# StationSolPortative.net
KiCad netlist of a schematic drawn in Altium Designer
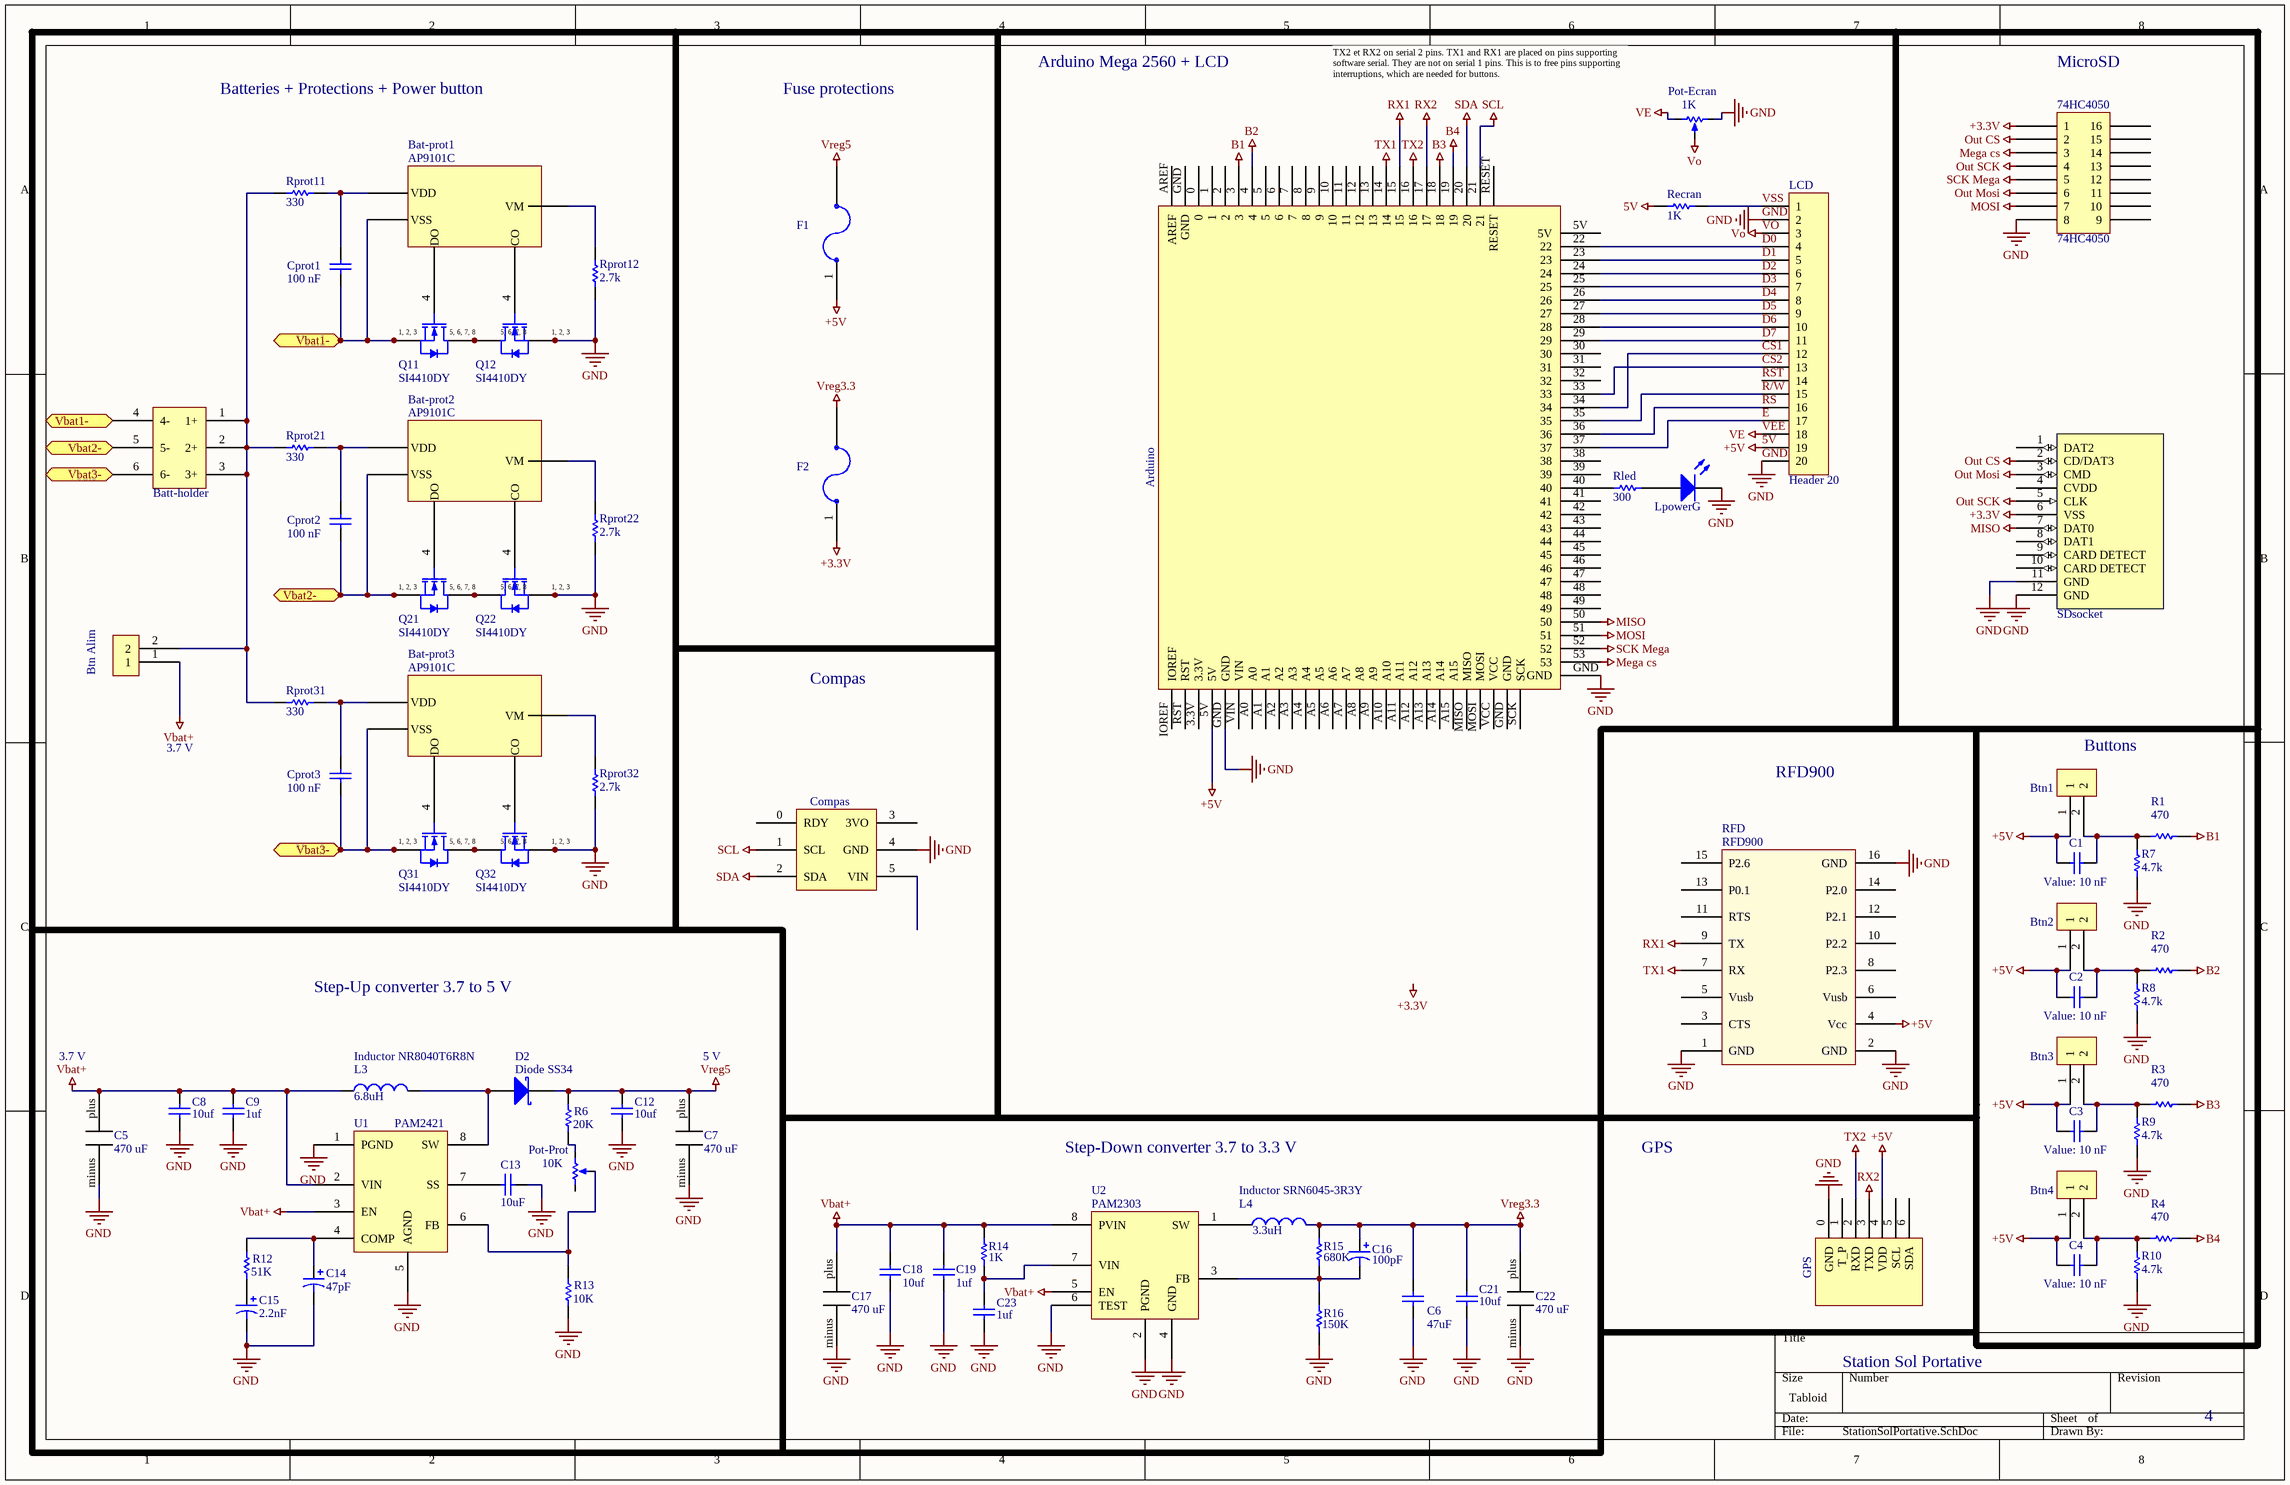
[diagram p0: StationSolPortative.SchDoc]

(export (version "E")
  (design (tool "Eeschema 10.0.6"))
  (components
    (comp (ref "74HC4050")
      (value "74HC4050")
      (footprint "DIP16_74HC4050")
      (libsource (lib "74HC4050") (part "74HC4050"))
    )
    (comp (ref "Arduino")
      (value "ArduinoMega2560")
      (footprint "ArduinoMega2560")
      (libsource (lib "ArduinoMega2560") (part "ArduinoMega2560"))
    )
    (comp (ref "Bat-prot1")
      (value "AP9101C")
      (footprint "SOT26")
      (fields (field (name "NAME") "AP9101C"))
      (libsource (lib "surfaceMount") (part "AP9101C"))
    )
    (comp (ref "Bat-prot2")
      (value "AP9101C")
      (footprint "SOT26")
      (fields (field (name "NAME") "AP9101C"))
      (libsource (lib "surfaceMount") (part "AP9101C"))
    )
    (comp (ref "Bat-prot3")
      (value "AP9101C")
      (footprint "SOT26")
      (fields (field (name "NAME") "AP9101C"))
      (libsource (lib "surfaceMount") (part "AP9101C"))
    )
    (comp (ref "Batt-holder")
      (value "BH-BK-18650-PC6-ND")
      (footprint "BH-BK-18650-PC6-ND")
      (libsource (lib "BatterieHolder") (part "BH-BK-18650-PC6-ND"))
    )
    (comp (ref "Btn Alim")
      (value "MAT100_2PINS")
      (footprint "MTA100_2PINS")
      (libsource (lib "MTA_connectors") (part "MAT100_2PINS"))
    )
    (comp (ref "Btn1")
      (value "MAT100_2PINS")
      (footprint "MTA100_2PINS")
      (libsource (lib "") (part "MAT100_2PINS_1"))
    )
    (comp (ref "Btn2")
      (value "MAT100_2PINS")
      (footprint "MTA100_2PINS")
      (libsource (lib "") (part "MAT100_2PINS_1"))
    )
    (comp (ref "Btn3")
      (value "MAT100_2PINS")
      (footprint "MTA100_2PINS")
      (libsource (lib "") (part "MAT100_2PINS_1"))
    )
    (comp (ref "Btn4")
      (value "MAT100_2PINS")
      (footprint "MTA100_2PINS")
      (libsource (lib "") (part "MAT100_2PINS_1"))
    )
    (comp (ref "C1")
      (value "10 nF")
      (footprint "CAP 0805 - N")
      (libsource (lib "surfaceMount") (part "Condensateur smd"))
    )
    (comp (ref "C2")
      (value "10 nF")
      (footprint "CAP 0805 - N")
      (libsource (lib "surfaceMount") (part "Condensateur smd"))
    )
    (comp (ref "C3")
      (value "10 nF")
      (footprint "CAP 0805 - N")
      (libsource (lib "surfaceMount") (part "Condensateur smd"))
    )
    (comp (ref "C4")
      (value "10 nF")
      (footprint "CAP 0805 - N")
      (libsource (lib "surfaceMount") (part "Condensateur smd"))
    )
    (comp (ref "C5")
      (value "470 uF")
      (footprint "Gros condensateur")
      (libsource (lib "surfaceMount") (part "Gros condensateur"))
    )
    (comp (ref "C6")
      (value "47uF")
      (footprint "C1210")
      (description "Capacitor (Semiconductor SIM Model)")
      (fields (field (name "Comment") "Cap Semi") (field (name "PUBLISHER") "Altium Limited"))
      (libsource (lib "Miscellaneous Devices") (part "Cap Semi"))
    )
    (comp (ref "C7")
      (value "470 uF")
      (footprint "Gros condensateur")
      (libsource (lib "surfaceMount") (part "Gros condensateur"))
    )
    (comp (ref "C8")
      (value "10uf")
      (footprint "CAP 0805 - N")
      (libsource (lib "surfaceMount") (part "Condensateur smd"))
    )
    (comp (ref "C9")
      (value "1uf")
      (footprint "CAP 0805 - N")
      (libsource (lib "surfaceMount") (part "Condensateur smd"))
    )
    (comp (ref "C12")
      (value "10uf")
      (footprint "CAP 0805 - N")
      (libsource (lib "surfaceMount") (part "Condensateur smd"))
    )
    (comp (ref "C13")
      (value "10uF")
      (footprint "CAP 0805 - N")
      (libsource (lib "surfaceMount") (part "Condensateur smd"))
    )
    (comp (ref "C14")
      (value "47pF")
      (footprint "CAP 0805 - N")
      (description "Polarized Capacitor (Radial)")
      (fields (field (name "Comment") "Cap Pol1") (field (name "PUBLISHER") "Altium Limited"))
      (libsource (lib "Miscellaneous Devices") (part "Cap Pol1"))
    )
    (comp (ref "C15")
      (value "2.2nF")
      (footprint "CAP 0805 - N")
      (description "Polarized Capacitor (Radial)")
      (fields (field (name "Comment") "Cap Pol1") (field (name "PUBLISHER") "Altium Limited"))
      (libsource (lib "Miscellaneous Devices") (part "Cap Pol1"))
    )
    (comp (ref "C16")
      (value "100pF")
      (footprint "CAP 0805 - N")
      (description "Polarized Capacitor (Radial)")
      (fields (field (name "Comment") "Cap Pol1") (field (name "PUBLISHER") "Altium Limited"))
      (libsource (lib "Miscellaneous Devices") (part "Cap Pol1"))
    )
    (comp (ref "C17")
      (value "470 uF")
      (footprint "Gros condensateur")
      (libsource (lib "surfaceMount") (part "Gros condensateur"))
    )
    (comp (ref "C18")
      (value "10uf")
      (footprint "CAP 0805 - N")
      (libsource (lib "surfaceMount") (part "Condensateur smd"))
    )
    (comp (ref "C19")
      (value "1uf")
      (footprint "CAP 0805 - N")
      (libsource (lib "surfaceMount") (part "Condensateur smd"))
    )
    (comp (ref "C21")
      (value "10uf")
      (footprint "CAP 0805 - N")
      (libsource (lib "surfaceMount") (part "Condensateur smd"))
    )
    (comp (ref "C22")
      (value "470 uF")
      (footprint "Gros condensateur")
      (libsource (lib "surfaceMount") (part "Gros condensateur"))
    )
    (comp (ref "C23")
      (value "1uf")
      (footprint "CAP 0805 - N")
      (libsource (lib "surfaceMount") (part "Condensateur smd"))
    )
    (comp (ref "Compas")
      (value "HMC5883L")
      (footprint "Adafruit:HMC5883L")
      (description "Compass")
      (libsource (lib "Adafruit") (part "HMC5883L"))
    )
    (comp (ref "Cprot1")
      (value "100 nF")
      (footprint "CAP 0805 - N")
      (libsource (lib "surfaceMount") (part "Condensateur smd"))
    )
    (comp (ref "Cprot2")
      (value "100 nF")
      (footprint "CAP 0805 - N")
      (libsource (lib "surfaceMount") (part "Condensateur smd"))
    )
    (comp (ref "Cprot3")
      (value "100 nF")
      (footprint "CAP 0805 - N")
      (libsource (lib "surfaceMount") (part "Condensateur smd"))
    )
    (comp (ref "D2")
      (value "Diode SS34")
      (footprint "Diode")
      (description "Schottky Rectifier")
      (fields (field (name "PUBLISHER") "Altium Limited"))
      (libsource (lib "Miscellaneous Devices") (part "Diode 10TQ035"))
    )
    (comp (ref "F1")
      (value "Fuse")
      (footprint "Fuse Holder 3mm")
      (libsource (lib "Lib Sch Compo") (part "Fuse"))
    )
    (comp (ref "F2")
      (value "Fuse")
      (footprint "Fuse Holder 3mm")
      (libsource (lib "Lib Sch Compo") (part "Fuse"))
    )
    (comp (ref "gps") (value "GPS") (footprint "PAM-7Q GPS") (libsource (lib "Paralax") (part "Pam-Q7 GPS")))
    (comp (ref "L3")
      (value "Inductor NR8040T6R8N")
      (footprint "Inductance 6.8uH")
      (description "Inductor")
      (fields (field (name "ALTIUM_VALUE") "6.8uH") (field (name "PUBLISHER") "Altium Limited"))
      (libsource (lib "Miscellaneous Devices") (part "Inductor"))
    )
    (comp (ref "L4")
      (value "Inductor SRN6045-3R3Y")
      (footprint "Inductance")
      (description "Inductor")
      (fields (field (name "ALTIUM_VALUE") "3.3uH") (field (name "PUBLISHER") "Altium Limited"))
      (libsource (lib "Miscellaneous Devices") (part "Inductor"))
    )
    (comp (ref "LCD")
      (value "Header 20")
      (footprint "Miscellaneous Connectors:HDR2X10")
      (description "Header, 20-Pin")
      (fields (field (name "PUBLISHER") "Altium Limited"))
      (libsource (lib "Miscellaneous Connectors") (part "Header 20"))
    )
    (comp (ref "LpowerG")
      (value "LED 1206")
      (footprint "LED - 1206")
      (libsource (lib "surfaceMount") (part "LED"))
    )
    (comp (ref "Pot-Ecran")
      (value "1K")
      (footprint "Trim 67WR")
      (description "Resistor Trimmer")
      (fields (field (name "Comment") "Res Pot"))
      (libsource (lib "Lib Sch Compo") (part "Res Pot"))
    )
    (comp (ref "Pot-Prot")
      (value "10K")
      (footprint "Trim 67WR")
      (description "Resistor Trimmer")
      (fields (field (name "Comment") "Res Pot"))
      (libsource (lib "Lib Sch Compo") (part "Res Pot"))
    )
    (comp (ref "Q11")
      (value "SI4410DY")
      (footprint "SO-8_N")
      (description "N-Channel 30V (D-S)  MOSFET")
      (fields (field (name "PUBLISHER") "Altium Limited"))
      (libsource (lib "Vishay Siliconix Discrete MOSFET") (part "SI4410DY"))
    )
    (comp (ref "Q12")
      (value "SI4410DY")
      (footprint "SO-8_N")
      (description "N-Channel 30V (D-S)  MOSFET")
      (fields (field (name "PUBLISHER") "Altium Limited"))
      (libsource (lib "Vishay Siliconix Discrete MOSFET") (part "SI4410DY"))
    )
    (comp (ref "Q21")
      (value "SI4410DY")
      (footprint "SO-8_N")
      (description "N-Channel 30V (D-S)  MOSFET")
      (fields (field (name "PUBLISHER") "Altium Limited"))
      (libsource (lib "Vishay Siliconix Discrete MOSFET") (part "SI4410DY"))
    )
    (comp (ref "Q22")
      (value "SI4410DY")
      (footprint "SO-8_N")
      (description "N-Channel 30V (D-S)  MOSFET")
      (fields (field (name "PUBLISHER") "Altium Limited"))
      (libsource (lib "Vishay Siliconix Discrete MOSFET") (part "SI4410DY"))
    )
    (comp (ref "Q31")
      (value "SI4410DY")
      (footprint "SO-8_N")
      (description "N-Channel 30V (D-S)  MOSFET")
      (fields (field (name "PUBLISHER") "Altium Limited"))
      (libsource (lib "Vishay Siliconix Discrete MOSFET") (part "SI4410DY"))
    )
    (comp (ref "Q32")
      (value "SI4410DY")
      (footprint "SO-8_N")
      (description "N-Channel 30V (D-S)  MOSFET")
      (fields (field (name "PUBLISHER") "Altium Limited"))
      (libsource (lib "Vishay Siliconix Discrete MOSFET") (part "SI4410DY"))
    )
    (comp (ref "R1")
      (value "470")
      (footprint "Res 0805 - N")
      (fields (field (name "Comment") "Res smd"))
      (libsource (lib "surfaceMount") (part "Res smd"))
    )
    (comp (ref "R2")
      (value "470")
      (footprint "Res 0805 - N")
      (fields (field (name "Comment") "Res smd"))
      (libsource (lib "surfaceMount") (part "Res smd"))
    )
    (comp (ref "R3")
      (value "470")
      (footprint "Res 0805 - N")
      (fields (field (name "Comment") "Res smd"))
      (libsource (lib "surfaceMount") (part "Res smd"))
    )
    (comp (ref "R4")
      (value "470")
      (footprint "Res 0805 - N")
      (fields (field (name "Comment") "Res smd"))
      (libsource (lib "surfaceMount") (part "Res smd"))
    )
    (comp (ref "R6")
      (value "20K")
      (footprint "Res 0805 - N")
      (description "Resistor")
      (fields (field (name "Comment") "Res1") (field (name "PUBLISHER") "Altium Limited"))
      (libsource (lib "Miscellaneous Devices") (part "Res1"))
    )
    (comp (ref "R7")
      (value "4.7k")
      (footprint "Res 0805 - N")
      (fields (field (name "Comment") "Res smd"))
      (libsource (lib "surfaceMount") (part "Res smd"))
    )
    (comp (ref "R8")
      (value "4.7k")
      (footprint "Res 0805 - N")
      (fields (field (name "Comment") "Res smd"))
      (libsource (lib "surfaceMount") (part "Res smd"))
    )
    (comp (ref "R9")
      (value "4.7k")
      (footprint "Res 0805 - N")
      (fields (field (name "Comment") "Res smd"))
      (libsource (lib "surfaceMount") (part "Res smd"))
    )
    (comp (ref "R10")
      (value "4.7k")
      (footprint "Res 0805 - N")
      (fields (field (name "Comment") "Res smd"))
      (libsource (lib "surfaceMount") (part "Res smd"))
    )
    (comp (ref "R12")
      (value "51K")
      (footprint "Res 0805 - N")
      (description "Resistor")
      (fields (field (name "Comment") "Res1") (field (name "PUBLISHER") "Altium Limited"))
      (libsource (lib "Miscellaneous Devices") (part "Res1"))
    )
    (comp (ref "R13")
      (value "10K")
      (footprint "Res 0805 - N")
      (description "Resistor")
      (fields (field (name "Comment") "Res1") (field (name "PUBLISHER") "Altium Limited"))
      (libsource (lib "Miscellaneous Devices") (part "Res1"))
    )
    (comp (ref "R14")
      (value "1K")
      (footprint "Res 0805 - N")
      (description "Resistor")
      (fields (field (name "Comment") "Res1") (field (name "PUBLISHER") "Altium Limited"))
      (libsource (lib "Miscellaneous Devices") (part "Res1"))
    )
    (comp (ref "R15")
      (value "680K")
      (footprint "Res 0805 - N")
      (description "Resistor")
      (fields (field (name "Comment") "Res1") (field (name "PUBLISHER") "Altium Limited"))
      (libsource (lib "Miscellaneous Devices") (part "Res1"))
    )
    (comp (ref "R16")
      (value "150K")
      (footprint "Res 0805 - N")
      (description "Resistor")
      (fields (field (name "Comment") "Res1") (field (name "PUBLISHER") "Altium Limited"))
      (libsource (lib "Miscellaneous Devices") (part "Res1"))
    )
    (comp (ref "Recran")
      (value "1K")
      (footprint "Res 0805 - N")
      (fields (field (name "Comment") "Res smd"))
      (libsource (lib "surfaceMount") (part "Res smd"))
    )
    (comp (ref "RFD")
      (value "Component_1")
      (footprint "RFD900")
      (libsource (lib "RFD900") (part "Component_1"))
    )
    (comp (ref "Rled")
      (value "300")
      (footprint "Res 0805 - N")
      (fields (field (name "Comment") "Res smd"))
      (libsource (lib "surfaceMount") (part "Res smd"))
    )
    (comp (ref "Rprot11")
      (value "330")
      (footprint "Res 0805 - N")
      (fields (field (name "Comment") "Res smd"))
      (libsource (lib "surfaceMount") (part "Res smd"))
    )
    (comp (ref "Rprot12")
      (value "2.7k")
      (footprint "Res 0805 - N")
      (fields (field (name "Comment") "Res smd"))
      (libsource (lib "surfaceMount") (part "Res smd"))
    )
    (comp (ref "Rprot21")
      (value "330")
      (footprint "Res 0805 - N")
      (fields (field (name "Comment") "Res smd"))
      (libsource (lib "surfaceMount") (part "Res smd"))
    )
    (comp (ref "Rprot22")
      (value "2.7k")
      (footprint "Res 0805 - N")
      (fields (field (name "Comment") "Res smd"))
      (libsource (lib "surfaceMount") (part "Res smd"))
    )
    (comp (ref "Rprot31")
      (value "330")
      (footprint "Res 0805 - N")
      (fields (field (name "Comment") "Res smd"))
      (libsource (lib "surfaceMount") (part "Res smd"))
    )
    (comp (ref "Rprot32")
      (value "2.7k")
      (footprint "Res 0805 - N")
      (fields (field (name "Comment") "Res smd"))
      (libsource (lib "surfaceMount") (part "Res smd"))
    )
    (comp (ref "SDsocket")
      (value "Carte micro SD")
      (footprint "Carte SD")
      (libsource (lib "surfaceMount") (part "Carte SD"))
    )
    (comp (ref "U1")
      (value "PAM2421")
      (footprint "SOP8")
      (description "3A PWM STEP-UP DC-DC CONVERTER")
      (fields (field (name "ALTIUM_UNNAMED_1") "PAM2421"))
      (libsource (lib "surfaceMount") (part "PAM2421"))
    )
    (comp (ref "U2")
      (value "PAM2320")
      (footprint "SOP8")
      (description "3A LOW NOISE STEP-DOWN DC-DC CONVERTER")
      (fields (field (name "NAME") "PAM2303"))
      (libsource (lib "PAM2303") (part "PAM2320"))
    )
  )
  (nets
    (net (code "1") (name "+3.3V") (class "Default")
      (node (ref "74HC4050") (pin "1") (pinfunction "1_1") (pintype "passive"))
      (node (ref "F2") (pin "1") (pinfunction "1_1") (pintype "passive"))
      (node (ref "SDsocket") (pin "6") (pinfunction "VSS_6") (pintype "power_in"))
    )
    (net (code "2") (name "+5V") (class "Default")
      (node (ref "Arduino") (pin "5V") (pinfunction "5V_5V") (pintype "passive"))
      (node (ref "Btn1") (pin "1") (pinfunction "1_1") (pintype "passive"))
      (node (ref "Btn2") (pin "1") (pinfunction "1_1") (pintype "passive"))
      (node (ref "Btn3") (pin "1") (pinfunction "1_1") (pintype "passive"))
      (node (ref "Btn4") (pin "1") (pinfunction "1_1") (pintype "passive"))
      (node (ref "C1") (pin "1") (pinfunction "1_1") (pintype "passive"))
      (node (ref "C2") (pin "1") (pinfunction "1_1") (pintype "passive"))
      (node (ref "C3") (pin "1") (pinfunction "1_1") (pintype "passive"))
      (node (ref "C4") (pin "1") (pinfunction "1_1") (pintype "passive"))
      (node (ref "F1") (pin "1") (pinfunction "1_1") (pintype "passive"))
      (node (ref "LCD") (pin "19") (pinfunction "19_19") (pintype "passive"))
      (node (ref "RFD") (pin "4") (pinfunction "Vcc_4") (pintype "passive"))
      (node (ref "Recran") (pin "1") (pinfunction "1_1") (pintype "passive"))
      (node (ref "gps") (pin "4") (pinfunction "VDD_4") (pintype "passive"))
    )
    (net (code "3") (name "/CS1") (class "Default")
      (node (ref "Arduino") (pin "34") (pinfunction "34_34") (pintype "passive"))
      (node (ref "LCD") (pin "12") (pinfunction "12_12") (pintype "passive"))
    )
    (net (code "4") (name "/CS2") (class "Default")
      (node (ref "Arduino") (pin "33") (pinfunction "33_33") (pintype "passive"))
      (node (ref "LCD") (pin "13") (pinfunction "13_13") (pintype "passive"))
    )
    (net (code "5") (name "/D0") (class "Default")
      (node (ref "Arduino") (pin "22") (pinfunction "22_22") (pintype "passive"))
      (node (ref "LCD") (pin "4") (pinfunction "4_4") (pintype "passive"))
    )
    (net (code "6") (name "/D1") (class "Default")
      (node (ref "Arduino") (pin "23") (pinfunction "23_23") (pintype "passive"))
      (node (ref "LCD") (pin "5") (pinfunction "5_5") (pintype "passive"))
    )
    (net (code "7") (name "/D2") (class "Default")
      (node (ref "Arduino") (pin "24") (pinfunction "24_24") (pintype "passive"))
      (node (ref "LCD") (pin "6") (pinfunction "6_6") (pintype "passive"))
    )
    (net (code "8") (name "/D3") (class "Default")
      (node (ref "Arduino") (pin "25") (pinfunction "25_25") (pintype "passive"))
      (node (ref "LCD") (pin "7") (pinfunction "7_7") (pintype "passive"))
    )
    (net (code "9") (name "/D4") (class "Default")
      (node (ref "Arduino") (pin "26") (pinfunction "26_26") (pintype "passive"))
      (node (ref "LCD") (pin "8") (pinfunction "8_8") (pintype "passive"))
    )
    (net (code "10") (name "/D5") (class "Default")
      (node (ref "Arduino") (pin "27") (pinfunction "27_27") (pintype "passive"))
      (node (ref "LCD") (pin "9") (pinfunction "9_9") (pintype "passive"))
    )
    (net (code "11") (name "/D6") (class "Default")
      (node (ref "Arduino") (pin "28") (pinfunction "28_28") (pintype "passive"))
      (node (ref "LCD") (pin "10") (pinfunction "10_10") (pintype "passive"))
    )
    (net (code "12") (name "/D7") (class "Default")
      (node (ref "Arduino") (pin "29") (pinfunction "29_29") (pintype "passive"))
      (node (ref "LCD") (pin "11") (pinfunction "11_11") (pintype "passive"))
    )
    (net (code "13") (name "/E") (class "Default")
      (node (ref "Arduino") (pin "37") (pinfunction "37_37") (pintype "passive"))
      (node (ref "LCD") (pin "17") (pinfunction "17_17") (pintype "passive"))
    )
    (net (code "14") (name "/RS") (class "Default")
      (node (ref "Arduino") (pin "36") (pinfunction "36_36") (pintype "passive"))
      (node (ref "LCD") (pin "16") (pinfunction "16_16") (pintype "passive"))
    )
    (net (code "15") (name "/RST") (class "Default")
      (node (ref "LCD") (pin "14") (pinfunction "14_14") (pintype "passive"))
    )
    (net (code "16") (name "/R{slash}W") (class "Default")
      (node (ref "Arduino") (pin "35") (pinfunction "35_35") (pintype "passive"))
      (node (ref "LCD") (pin "15") (pinfunction "15_15") (pintype "passive"))
    )
    (net (code "17") (name "/VSS") (class "Default")
      (node (ref "LCD") (pin "1") (pinfunction "1_1") (pintype "passive"))
      (node (ref "Recran") (pin "2") (pinfunction "2_2") (pintype "passive"))
    )
    (net (code "18") (name "/Vbat1-") (class "Default")
      (node (ref "Bat-prot1") (pin "VSS") (pinfunction "VSS_VSS") (pintype "passive"))
      (node (ref "Batt-holder") (pin "4") (pinfunction "4-_4") (pintype "passive"))
      (node (ref "Cprot1") (pin "1") (pinfunction "1_1") (pintype "passive"))
      (node (ref "Q11") (pin "1") (pinfunction "S_1") (pintype "passive"))
      (node (ref "Q11") (pin "2") (pinfunction "S_2") (pintype "passive"))
      (node (ref "Q11") (pin "3") (pinfunction "S_3") (pintype "passive"))
    )
    (net (code "19") (name "/Vbat2-") (class "Default")
      (node (ref "Bat-prot2") (pin "VSS") (pinfunction "VSS_VSS") (pintype "passive"))
      (node (ref "Batt-holder") (pin "5") (pinfunction "5-_5") (pintype "passive"))
      (node (ref "Cprot2") (pin "1") (pinfunction "1_1") (pintype "passive"))
      (node (ref "Q21") (pin "1") (pinfunction "S_1") (pintype "passive"))
      (node (ref "Q21") (pin "2") (pinfunction "S_2") (pintype "passive"))
      (node (ref "Q21") (pin "3") (pinfunction "S_3") (pintype "passive"))
    )
    (net (code "20") (name "/Vbat3-") (class "Default")
      (node (ref "Bat-prot3") (pin "VSS") (pinfunction "VSS_VSS") (pintype "passive"))
      (node (ref "Batt-holder") (pin "6") (pinfunction "6-_6") (pintype "passive"))
      (node (ref "Cprot3") (pin "1") (pinfunction "1_1") (pintype "passive"))
      (node (ref "Q31") (pin "1") (pinfunction "S_1") (pintype "passive"))
      (node (ref "Q31") (pin "2") (pinfunction "S_2") (pintype "passive"))
      (node (ref "Q31") (pin "3") (pinfunction "S_3") (pintype "passive"))
    )
    (net (code "21") (name "B1") (class "Default")
      (node (ref "Arduino") (pin "3") (pinfunction "3_3") (pintype "passive"))
      (node (ref "R1") (pin "1") (pinfunction "1_1") (pintype "passive"))
    )
    (net (code "22") (name "B2") (class "Default")
      (node (ref "Arduino") (pin "4") (pinfunction "4_4") (pintype "passive"))
      (node (ref "R2") (pin "1") (pinfunction "1_1") (pintype "passive"))
    )
    (net (code "23") (name "B3") (class "Default")
      (node (ref "Arduino") (pin "18") (pinfunction "18_18") (pintype "passive"))
      (node (ref "R3") (pin "1") (pinfunction "1_1") (pintype "passive"))
    )
    (net (code "24") (name "B4") (class "Default")
      (node (ref "Arduino") (pin "19") (pinfunction "19_19") (pintype "passive"))
      (node (ref "R4") (pin "1") (pinfunction "1_1") (pintype "passive"))
    )
    (net (code "25") (name "GND") (class "Default")
      (node (ref "74HC4050") (pin "8") (pinfunction "8_8") (pintype "passive"))
      (node (ref "Arduino") (pin "GND") (pinfunction "GND_GND") (pintype "passive"))
      (node (ref "C12") (pin "1") (pinfunction "1_1") (pintype "passive"))
      (node (ref "C13") (pin "1") (pinfunction "1_1") (pintype "passive"))
      (node (ref "C14") (pin "2") (pinfunction "2_2") (pintype "passive"))
      (node (ref "C15") (pin "2") (pinfunction "2_2") (pintype "passive"))
      (node (ref "C17") (pin "minus") (pinfunction "minus_minus") (pintype "passive"))
      (node (ref "C18") (pin "1") (pinfunction "1_1") (pintype "passive"))
      (node (ref "C19") (pin "1") (pinfunction "1_1") (pintype "passive"))
      (node (ref "C21") (pin "1") (pinfunction "1_1") (pintype "passive"))
      (node (ref "C22") (pin "minus") (pinfunction "minus_minus") (pintype "passive"))
      (node (ref "C23") (pin "1") (pinfunction "1_1") (pintype "passive"))
      (node (ref "C5") (pin "minus") (pinfunction "minus_minus") (pintype "passive"))
      (node (ref "C6") (pin "1") (pinfunction "1_1") (pintype "passive"))
      (node (ref "C7") (pin "minus") (pinfunction "minus_minus") (pintype "passive"))
      (node (ref "C8") (pin "1") (pinfunction "1_1") (pintype "passive"))
      (node (ref "C9") (pin "1") (pinfunction "1_1") (pintype "passive"))
      (node (ref "Compas") (pin "4") (pinfunction "GND_4") (pintype "passive"))
      (node (ref "LCD") (pin "2") (pinfunction "2_2") (pintype "passive"))
      (node (ref "LCD") (pin "20") (pinfunction "20_20") (pintype "passive"))
      (node (ref "LpowerG") (pin "2") (pinfunction "2_2") (pintype "passive"))
      (node (ref "Pot-Ecran") (pin "3") (pinfunction "Bot_3") (pintype "passive"))
      (node (ref "Q12") (pin "1") (pinfunction "S_1") (pintype "passive"))
      (node (ref "Q12") (pin "2") (pinfunction "S_2") (pintype "passive"))
      (node (ref "Q12") (pin "3") (pinfunction "S_3") (pintype "passive"))
      (node (ref "Q22") (pin "1") (pinfunction "S_1") (pintype "passive"))
      (node (ref "Q22") (pin "2") (pinfunction "S_2") (pintype "passive"))
      (node (ref "Q22") (pin "3") (pinfunction "S_3") (pintype "passive"))
      (node (ref "Q32") (pin "1") (pinfunction "S_1") (pintype "passive"))
      (node (ref "Q32") (pin "2") (pinfunction "S_2") (pintype "passive"))
      (node (ref "Q32") (pin "3") (pinfunction "S_3") (pintype "passive"))
      (node (ref "R10") (pin "1") (pinfunction "1_1") (pintype "passive"))
      (node (ref "R13") (pin "1") (pinfunction "1_1") (pintype "passive"))
      (node (ref "R16") (pin "1") (pinfunction "1_1") (pintype "passive"))
      (node (ref "R7") (pin "1") (pinfunction "1_1") (pintype "passive"))
      (node (ref "R8") (pin "1") (pinfunction "1_1") (pintype "passive"))
      (node (ref "R9") (pin "1") (pinfunction "1_1") (pintype "passive"))
      (node (ref "RFD") (pin "1") (pinfunction "GND_1") (pintype "passive"))
      (node (ref "RFD") (pin "16") (pinfunction "GND_16") (pintype "passive"))
      (node (ref "RFD") (pin "2") (pinfunction "GND_2") (pintype "passive"))
      (node (ref "Rprot12") (pin "1") (pinfunction "1_1") (pintype "passive"))
      (node (ref "Rprot22") (pin "1") (pinfunction "1_1") (pintype "passive"))
      (node (ref "Rprot32") (pin "1") (pinfunction "1_1") (pintype "passive"))
      (node (ref "SDsocket") (pin "11") (pinfunction "GND_11") (pintype "power_in"))
      (node (ref "SDsocket") (pin "12") (pinfunction "GND_12") (pintype "power_in"))
      (node (ref "U1") (pin "1") (pinfunction "PGND_1") (pintype "passive"))
      (node (ref "U1") (pin "5") (pinfunction "AGND_5") (pintype "passive"))
      (node (ref "U2") (pin "2") (pinfunction "PGND_2") (pintype "passive"))
      (node (ref "U2") (pin "4") (pinfunction "GND_4") (pintype "passive"))
      (node (ref "U2") (pin "6") (pinfunction "TEST_6") (pintype "passive"))
      (node (ref "gps") (pin "0") (pinfunction "GND_0") (pintype "passive"))
    )
    (net (code "26") (name "MISO") (class "Default")
      (node (ref "Arduino") (pin "50") (pinfunction "50_50") (pintype "passive"))
      (node (ref "SDsocket") (pin "7") (pinfunction "DAT0_7") (pintype "bidirectional"))
    )
    (net (code "27") (name "MOSI") (class "Default")
      (node (ref "74HC4050") (pin "7") (pinfunction "7_7") (pintype "passive"))
      (node (ref "Arduino") (pin "51") (pinfunction "51_51") (pintype "passive"))
    )
    (net (code "28") (name "Mega cs") (class "Default")
      (node (ref "74HC4050") (pin "3") (pinfunction "3_3") (pintype "passive"))
      (node (ref "Arduino") (pin "53") (pinfunction "53_53") (pintype "passive"))
    )
    (net (code "29") (name "Net-(Arduino-Pad40)") (class "Default")
      (node (ref "Arduino") (pin "40") (pinfunction "40_40") (pintype "passive"))
      (node (ref "Rled") (pin "1") (pinfunction "1_1") (pintype "passive"))
    )
    (net (code "30") (name "Net-(Bat-prot1-PadVDD)") (class "Default")
      (node (ref "Bat-prot1") (pin "VDD") (pinfunction "VDD_VDD") (pintype "passive"))
      (node (ref "Cprot1") (pin "2") (pinfunction "2_2") (pintype "passive"))
      (node (ref "Rprot11") (pin "2") (pinfunction "2_2") (pintype "passive"))
    )
    (net (code "31") (name "Net-(Bat-prot1-PadVM)") (class "Default")
      (node (ref "Bat-prot1") (pin "VM") (pinfunction "VM_VM") (pintype "passive"))
      (node (ref "Rprot12") (pin "2") (pinfunction "2_2") (pintype "passive"))
    )
    (net (code "32") (name "Net-(Bat-prot2-PadVDD)") (class "Default")
      (node (ref "Bat-prot2") (pin "VDD") (pinfunction "VDD_VDD") (pintype "passive"))
      (node (ref "Cprot2") (pin "2") (pinfunction "2_2") (pintype "passive"))
      (node (ref "Rprot21") (pin "2") (pinfunction "2_2") (pintype "passive"))
    )
    (net (code "33") (name "Net-(Bat-prot2-PadVM)") (class "Default")
      (node (ref "Bat-prot2") (pin "VM") (pinfunction "VM_VM") (pintype "passive"))
      (node (ref "Rprot22") (pin "2") (pinfunction "2_2") (pintype "passive"))
    )
    (net (code "34") (name "Net-(Bat-prot3-PadVDD)") (class "Default")
      (node (ref "Bat-prot3") (pin "VDD") (pinfunction "VDD_VDD") (pintype "passive"))
      (node (ref "Cprot3") (pin "2") (pinfunction "2_2") (pintype "passive"))
      (node (ref "Rprot31") (pin "2") (pinfunction "2_2") (pintype "passive"))
    )
    (net (code "35") (name "Net-(Bat-prot3-PadVM)") (class "Default")
      (node (ref "Bat-prot3") (pin "VM") (pinfunction "VM_VM") (pintype "passive"))
      (node (ref "Rprot32") (pin "2") (pinfunction "2_2") (pintype "passive"))
    )
    (net (code "36") (name "Net-(Batt-holder-1+)") (class "Default")
      (node (ref "Batt-holder") (pin "1") (pinfunction "1+_1") (pintype "passive"))
      (node (ref "Batt-holder") (pin "2") (pinfunction "2+_2") (pintype "passive"))
      (node (ref "Batt-holder") (pin "3") (pinfunction "3+_3") (pintype "passive"))
      (node (ref "Btn Alim") (pin "2") (pinfunction "2_2") (pintype "passive"))
      (node (ref "Rprot11") (pin "1") (pinfunction "1_1") (pintype "passive"))
      (node (ref "Rprot21") (pin "1") (pinfunction "1_1") (pintype "passive"))
      (node (ref "Rprot31") (pin "1") (pinfunction "1_1") (pintype "passive"))
    )
    (net (code "37") (name "Net-(Btn1-Pad2)") (class "Default")
      (node (ref "Btn1") (pin "2") (pinfunction "2_2") (pintype "passive"))
      (node (ref "C1") (pin "2") (pinfunction "2_2") (pintype "passive"))
      (node (ref "R1") (pin "2") (pinfunction "2_2") (pintype "passive"))
      (node (ref "R7") (pin "2") (pinfunction "2_2") (pintype "passive"))
    )
    (net (code "38") (name "Net-(Btn2-Pad2)") (class "Default")
      (node (ref "Btn2") (pin "2") (pinfunction "2_2") (pintype "passive"))
      (node (ref "C2") (pin "2") (pinfunction "2_2") (pintype "passive"))
      (node (ref "R2") (pin "2") (pinfunction "2_2") (pintype "passive"))
      (node (ref "R8") (pin "2") (pinfunction "2_2") (pintype "passive"))
    )
    (net (code "39") (name "Net-(Btn3-Pad2)") (class "Default")
      (node (ref "Btn3") (pin "2") (pinfunction "2_2") (pintype "passive"))
      (node (ref "C3") (pin "2") (pinfunction "2_2") (pintype "passive"))
      (node (ref "R3") (pin "2") (pinfunction "2_2") (pintype "passive"))
      (node (ref "R9") (pin "2") (pinfunction "2_2") (pintype "passive"))
    )
    (net (code "40") (name "Net-(Btn4-Pad2)") (class "Default")
      (node (ref "Btn4") (pin "2") (pinfunction "2_2") (pintype "passive"))
      (node (ref "C4") (pin "2") (pinfunction "2_2") (pintype "passive"))
      (node (ref "R10") (pin "2") (pinfunction "2_2") (pintype "passive"))
      (node (ref "R4") (pin "2") (pinfunction "2_2") (pintype "passive"))
    )
    (net (code "41") (name "Net-(C15-Pad1)") (class "Default")
      (node (ref "C15") (pin "1") (pinfunction "1_1") (pintype "passive"))
      (node (ref "R12") (pin "1") (pinfunction "1_1") (pintype "passive"))
    )
    (net (code "42") (name "Net-(D2-A)") (class "Default")
      (node (ref "D2") (pin "3") (pinfunction "A_3") (pintype "passive"))
      (node (ref "L3") (pin "2") (pinfunction "2_2") (pintype "passive"))
      (node (ref "U1") (pin "8") (pinfunction "SW_8") (pintype "passive"))
    )
    (net (code "43") (name "Net-(LpowerG-Pad1)") (class "Default")
      (node (ref "LpowerG") (pin "1") (pinfunction "1_1") (pintype "passive"))
      (node (ref "Rled") (pin "2") (pinfunction "2_2") (pintype "passive"))
    )
    (net (code "44") (name "Net-(Pot-Prot-Bot)") (class "Default")
      (node (ref "Pot-Prot") (pin "3") (pinfunction "Bot_3") (pintype "passive"))
      (node (ref "R6") (pin "1") (pinfunction "1_1") (pintype "passive"))
    )
    (net (code "45") (name "Net-(Pot-Prot-Tap)") (class "Default")
      (node (ref "Pot-Prot") (pin "2") (pinfunction "Tap_2") (pintype "passive"))
      (node (ref "R13") (pin "2") (pinfunction "2_2") (pintype "passive"))
      (node (ref "U1") (pin "6") (pinfunction "FB_6") (pintype "passive"))
    )
    (net (code "46") (name "Net-(Q11-D-Pad5)") (class "Default")
      (node (ref "Q11") (pin "5") (pinfunction "D_5") (pintype "passive"))
      (node (ref "Q11") (pin "6") (pinfunction "D_6") (pintype "passive"))
      (node (ref "Q11") (pin "7") (pinfunction "D_7") (pintype "passive"))
      (node (ref "Q11") (pin "8") (pinfunction "D_8") (pintype "passive"))
      (node (ref "Q12") (pin "5") (pinfunction "D_5") (pintype "passive"))
      (node (ref "Q12") (pin "6") (pinfunction "D_6") (pintype "passive"))
      (node (ref "Q12") (pin "7") (pinfunction "D_7") (pintype "passive"))
      (node (ref "Q12") (pin "8") (pinfunction "D_8") (pintype "passive"))
    )
    (net (code "47") (name "Net-(Q11-G)") (class "Default")
      (node (ref "Bat-prot1") (pin "DO") (pinfunction "DO_DO") (pintype "passive"))
      (node (ref "Q11") (pin "4") (pinfunction "G_4") (pintype "passive"))
    )
    (net (code "48") (name "Net-(Q12-G)") (class "Default")
      (node (ref "Bat-prot1") (pin "CO") (pinfunction "CO_CO") (pintype "passive"))
      (node (ref "Q12") (pin "4") (pinfunction "G_4") (pintype "passive"))
    )
    (net (code "49") (name "Net-(Q21-D-Pad5)") (class "Default")
      (node (ref "Q21") (pin "5") (pinfunction "D_5") (pintype "passive"))
      (node (ref "Q21") (pin "6") (pinfunction "D_6") (pintype "passive"))
      (node (ref "Q21") (pin "7") (pinfunction "D_7") (pintype "passive"))
      (node (ref "Q21") (pin "8") (pinfunction "D_8") (pintype "passive"))
      (node (ref "Q22") (pin "5") (pinfunction "D_5") (pintype "passive"))
      (node (ref "Q22") (pin "6") (pinfunction "D_6") (pintype "passive"))
      (node (ref "Q22") (pin "7") (pinfunction "D_7") (pintype "passive"))
      (node (ref "Q22") (pin "8") (pinfunction "D_8") (pintype "passive"))
    )
    (net (code "50") (name "Net-(Q21-G)") (class "Default")
      (node (ref "Bat-prot2") (pin "DO") (pinfunction "DO_DO") (pintype "passive"))
      (node (ref "Q21") (pin "4") (pinfunction "G_4") (pintype "passive"))
    )
    (net (code "51") (name "Net-(Q22-G)") (class "Default")
      (node (ref "Bat-prot2") (pin "CO") (pinfunction "CO_CO") (pintype "passive"))
      (node (ref "Q22") (pin "4") (pinfunction "G_4") (pintype "passive"))
    )
    (net (code "52") (name "Net-(Q31-D-Pad5)") (class "Default")
      (node (ref "Q31") (pin "5") (pinfunction "D_5") (pintype "passive"))
      (node (ref "Q31") (pin "6") (pinfunction "D_6") (pintype "passive"))
      (node (ref "Q31") (pin "7") (pinfunction "D_7") (pintype "passive"))
      (node (ref "Q31") (pin "8") (pinfunction "D_8") (pintype "passive"))
      (node (ref "Q32") (pin "5") (pinfunction "D_5") (pintype "passive"))
      (node (ref "Q32") (pin "6") (pinfunction "D_6") (pintype "passive"))
      (node (ref "Q32") (pin "7") (pinfunction "D_7") (pintype "passive"))
      (node (ref "Q32") (pin "8") (pinfunction "D_8") (pintype "passive"))
    )
    (net (code "53") (name "Net-(Q31-G)") (class "Default")
      (node (ref "Bat-prot3") (pin "DO") (pinfunction "DO_DO") (pintype "passive"))
      (node (ref "Q31") (pin "4") (pinfunction "G_4") (pintype "passive"))
    )
    (net (code "54") (name "Net-(Q32-G)") (class "Default")
      (node (ref "Bat-prot3") (pin "CO") (pinfunction "CO_CO") (pintype "passive"))
      (node (ref "Q32") (pin "4") (pinfunction "G_4") (pintype "passive"))
    )
    (net (code "55") (name "Net-(U1-COMP)") (class "Default")
      (node (ref "C14") (pin "1") (pinfunction "1_1") (pintype "passive"))
      (node (ref "R12") (pin "2") (pinfunction "2_2") (pintype "passive"))
      (node (ref "U1") (pin "4") (pinfunction "COMP_4") (pintype "passive"))
    )
    (net (code "56") (name "Net-(U1-SS)") (class "Default")
      (node (ref "C13") (pin "2") (pinfunction "2_2") (pintype "passive"))
      (node (ref "U1") (pin "7") (pinfunction "SS_7") (pintype "passive"))
    )
    (net (code "57") (name "Net-(U2-FB)") (class "Default")
      (node (ref "C16") (pin "2") (pinfunction "2_2") (pintype "passive"))
      (node (ref "R15") (pin "1") (pinfunction "1_1") (pintype "passive"))
      (node (ref "R16") (pin "2") (pinfunction "2_2") (pintype "passive"))
      (node (ref "U2") (pin "3") (pinfunction "FB_3") (pintype "passive"))
    )
    (net (code "58") (name "Net-(U2-SW)") (class "Default")
      (node (ref "L4") (pin "1") (pinfunction "1_1") (pintype "passive"))
      (node (ref "U2") (pin "1") (pinfunction "SW_1") (pintype "passive"))
    )
    (net (code "59") (name "Net-(U2-VIN)") (class "Default")
      (node (ref "C23") (pin "2") (pinfunction "2_2") (pintype "passive"))
      (node (ref "R14") (pin "1") (pinfunction "1_1") (pintype "passive"))
      (node (ref "U2") (pin "7") (pinfunction "VIN_7") (pintype "passive"))
    )
    (net (code "60") (name "Out CS") (class "Default")
      (node (ref "74HC4050") (pin "2") (pinfunction "2_2") (pintype "passive"))
      (node (ref "SDsocket") (pin "2") (pinfunction "CD/DAT3_2") (pintype "bidirectional"))
    )
    (net (code "61") (name "Out Mosi") (class "Default")
      (node (ref "74HC4050") (pin "6") (pinfunction "6_6") (pintype "passive"))
      (node (ref "SDsocket") (pin "3") (pinfunction "CMD_3") (pintype "bidirectional"))
    )
    (net (code "62") (name "Out SCK") (class "Default")
      (node (ref "74HC4050") (pin "4") (pinfunction "4_4") (pintype "passive"))
      (node (ref "SDsocket") (pin "5") (pinfunction "CLK_5") (pintype "input"))
    )
    (net (code "63") (name "RX1") (class "Default")
      (node (ref "Arduino") (pin "15") (pinfunction "15_15") (pintype "passive"))
      (node (ref "RFD") (pin "9") (pinfunction "TX_9") (pintype "passive"))
    )
    (net (code "64") (name "RX2") (class "Default")
      (node (ref "Arduino") (pin "17") (pinfunction "17_17") (pintype "passive"))
      (node (ref "gps") (pin "3") (pinfunction "TXD_3") (pintype "passive"))
    )
    (net (code "65") (name "SCK Mega") (class "Default")
      (node (ref "74HC4050") (pin "5") (pinfunction "5_5") (pintype "passive"))
      (node (ref "Arduino") (pin "52") (pinfunction "52_52") (pintype "passive"))
    )
    (net (code "66") (name "SCL") (class "Default")
      (node (ref "Arduino") (pin "21") (pinfunction "21_21") (pintype "passive"))
      (node (ref "Compas") (pin "1") (pinfunction "SCL_1") (pintype "passive"))
    )
    (net (code "67") (name "SDA") (class "Default")
      (node (ref "Arduino") (pin "20") (pinfunction "20_20") (pintype "passive"))
      (node (ref "Compas") (pin "2") (pinfunction "SDA_2") (pintype "passive"))
    )
    (net (code "68") (name "TX1") (class "Default")
      (node (ref "Arduino") (pin "14") (pinfunction "14_14") (pintype "passive"))
      (node (ref "RFD") (pin "7") (pinfunction "RX_7") (pintype "passive"))
    )
    (net (code "69") (name "TX2") (class "Default")
      (node (ref "Arduino") (pin "16") (pinfunction "16_16") (pintype "passive"))
      (node (ref "gps") (pin "2") (pinfunction "RXD_2") (pintype "passive"))
    )
    (net (code "70") (name "VE") (class "Default")
      (node (ref "LCD") (pin "18") (pinfunction "18_18") (pintype "passive"))
      (node (ref "Pot-Ecran") (pin "1") (pinfunction "Top_1") (pintype "passive"))
    )
    (net (code "71") (name "Vbat+") (class "Default")
      (node (ref "Btn Alim") (pin "1") (pinfunction "1_1") (pintype "passive"))
      (node (ref "C17") (pin "plus") (pinfunction "plus_plus") (pintype "passive"))
      (node (ref "C18") (pin "2") (pinfunction "2_2") (pintype "passive"))
      (node (ref "C19") (pin "2") (pinfunction "2_2") (pintype "passive"))
      (node (ref "C5") (pin "plus") (pinfunction "plus_plus") (pintype "passive"))
      (node (ref "C8") (pin "2") (pinfunction "2_2") (pintype "passive"))
      (node (ref "C9") (pin "2") (pinfunction "2_2") (pintype "passive"))
      (node (ref "L3") (pin "1") (pinfunction "1_1") (pintype "passive"))
      (node (ref "R14") (pin "2") (pinfunction "2_2") (pintype "passive"))
      (node (ref "U1") (pin "2") (pinfunction "VIN_2") (pintype "passive"))
      (node (ref "U1") (pin "3") (pinfunction "EN_3") (pintype "passive"))
      (node (ref "U2") (pin "5") (pinfunction "EN_5") (pintype "passive"))
      (node (ref "U2") (pin "8") (pinfunction "PVIN_8") (pintype "passive"))
    )
    (net (code "72") (name "Vo") (class "Default")
      (node (ref "LCD") (pin "3") (pinfunction "3_3") (pintype "passive"))
      (node (ref "Pot-Ecran") (pin "2") (pinfunction "Tap_2") (pintype "passive"))
    )
    (net (code "73") (name "Vreg3.3") (class "Default")
      (node (ref "C16") (pin "1") (pinfunction "1_1") (pintype "passive"))
      (node (ref "C21") (pin "2") (pinfunction "2_2") (pintype "passive"))
      (node (ref "C22") (pin "plus") (pinfunction "plus_plus") (pintype "passive"))
      (node (ref "C6") (pin "2") (pinfunction "2_2") (pintype "passive"))
      (node (ref "F2") (pin "2") (pinfunction "2_2") (pintype "passive"))
      (node (ref "L4") (pin "2") (pinfunction "2_2") (pintype "passive"))
      (node (ref "R15") (pin "2") (pinfunction "2_2") (pintype "passive"))
    )
    (net (code "74") (name "Vreg5") (class "Default")
      (node (ref "C12") (pin "2") (pinfunction "2_2") (pintype "passive"))
      (node (ref "C7") (pin "plus") (pinfunction "plus_plus") (pintype "passive"))
      (node (ref "D2") (pin "1") (pinfunction "K_1") (pintype "passive"))
      (node (ref "F1") (pin "2") (pinfunction "2_2") (pintype "passive"))
      (node (ref "R6") (pin "2") (pinfunction "2_2") (pintype "passive"))
    )
    (net (code "75") (name "unconnected-(74HC4050-Pad9)") (class "Default")
      (node (ref "74HC4050") (pin "9") (pinfunction "9_9") (pintype "passive"))
    )
    (net (code "76") (name "unconnected-(74HC4050-Pad10)") (class "Default")
      (node (ref "74HC4050") (pin "10") (pinfunction "10_10") (pintype "passive"))
    )
    (net (code "77") (name "unconnected-(74HC4050-Pad11)") (class "Default")
      (node (ref "74HC4050") (pin "11") (pinfunction "11_11") (pintype "passive"))
    )
    (net (code "78") (name "unconnected-(74HC4050-Pad12)") (class "Default")
      (node (ref "74HC4050") (pin "12") (pinfunction "12_12") (pintype "passive"))
    )
    (net (code "79") (name "unconnected-(74HC4050-Pad13)") (class "Default")
      (node (ref "74HC4050") (pin "13") (pinfunction "13_13") (pintype "passive"))
    )
    (net (code "80") (name "unconnected-(74HC4050-Pad14)") (class "Default")
      (node (ref "74HC4050") (pin "14") (pinfunction "14_14") (pintype "passive"))
    )
    (net (code "81") (name "unconnected-(74HC4050-Pad15)") (class "Default")
      (node (ref "74HC4050") (pin "15") (pinfunction "15_15") (pintype "passive"))
    )
    (net (code "82") (name "unconnected-(74HC4050-Pad16)") (class "Default")
      (node (ref "74HC4050") (pin "16") (pinfunction "16_16") (pintype "passive"))
    )
    (net (code "83") (name "unconnected-(Arduino-Pad0)") (class "Default")
      (node (ref "Arduino") (pin "0") (pinfunction "0_0") (pintype "passive"))
    )
    (net (code "84") (name "unconnected-(Arduino-Pad1)") (class "Default")
      (node (ref "Arduino") (pin "1") (pinfunction "1_1") (pintype "passive"))
    )
    (net (code "85") (name "unconnected-(Arduino-Pad2)") (class "Default")
      (node (ref "Arduino") (pin "2") (pinfunction "2_2") (pintype "passive"))
    )
    (net (code "86") (name "unconnected-(Arduino-Pad3.3V)") (class "Default")
      (node (ref "Arduino") (pin "3.3V") (pinfunction "3.3V_3.3V") (pintype "passive"))
    )
    (net (code "87") (name "unconnected-(Arduino-Pad5)") (class "Default")
      (node (ref "Arduino") (pin "5") (pinfunction "5_5") (pintype "passive"))
    )
    (net (code "88") (name "unconnected-(Arduino-Pad5V)") (class "Default")
      (node (ref "Arduino") (pin "5V") (pinfunction "5V_5V") (pintype "passive"))
    )
    (net (code "89") (name "unconnected-(Arduino-Pad6)") (class "Default")
      (node (ref "Arduino") (pin "6") (pinfunction "6_6") (pintype "passive"))
    )
    (net (code "90") (name "unconnected-(Arduino-Pad7)") (class "Default")
      (node (ref "Arduino") (pin "7") (pinfunction "7_7") (pintype "passive"))
    )
    (net (code "91") (name "unconnected-(Arduino-Pad8)") (class "Default")
      (node (ref "Arduino") (pin "8") (pinfunction "8_8") (pintype "passive"))
    )
    (net (code "92") (name "unconnected-(Arduino-Pad9)") (class "Default")
      (node (ref "Arduino") (pin "9") (pinfunction "9_9") (pintype "passive"))
    )
    (net (code "93") (name "unconnected-(Arduino-Pad10)") (class "Default")
      (node (ref "Arduino") (pin "10") (pinfunction "10_10") (pintype "passive"))
    )
    (net (code "94") (name "unconnected-(Arduino-Pad11)") (class "Default")
      (node (ref "Arduino") (pin "11") (pinfunction "11_11") (pintype "passive"))
    )
    (net (code "95") (name "unconnected-(Arduino-Pad12)") (class "Default")
      (node (ref "Arduino") (pin "12") (pinfunction "12_12") (pintype "passive"))
    )
    (net (code "96") (name "unconnected-(Arduino-Pad13)") (class "Default")
      (node (ref "Arduino") (pin "13") (pinfunction "13_13") (pintype "passive"))
    )
    (net (code "97") (name "unconnected-(Arduino-Pad30)") (class "Default")
      (node (ref "Arduino") (pin "30") (pinfunction "30_30") (pintype "passive"))
    )
    (net (code "98") (name "unconnected-(Arduino-Pad31)") (class "Default")
      (node (ref "Arduino") (pin "31") (pinfunction "31_31") (pintype "passive"))
    )
    (net (code "99") (name "unconnected-(Arduino-Pad32)") (class "Default")
      (node (ref "Arduino") (pin "32") (pinfunction "32_32") (pintype "passive"))
    )
    (net (code "100") (name "unconnected-(Arduino-Pad38)") (class "Default")
      (node (ref "Arduino") (pin "38") (pinfunction "38_38") (pintype "passive"))
    )
    (net (code "101") (name "unconnected-(Arduino-Pad39)") (class "Default")
      (node (ref "Arduino") (pin "39") (pinfunction "39_39") (pintype "passive"))
    )
    (net (code "102") (name "unconnected-(Arduino-Pad41)") (class "Default")
      (node (ref "Arduino") (pin "41") (pinfunction "41_41") (pintype "passive"))
    )
    (net (code "103") (name "unconnected-(Arduino-Pad42)") (class "Default")
      (node (ref "Arduino") (pin "42") (pinfunction "42_42") (pintype "passive"))
    )
    (net (code "104") (name "unconnected-(Arduino-Pad43)") (class "Default")
      (node (ref "Arduino") (pin "43") (pinfunction "43_43") (pintype "passive"))
    )
    (net (code "105") (name "unconnected-(Arduino-Pad44)") (class "Default")
      (node (ref "Arduino") (pin "44") (pinfunction "44_44") (pintype "passive"))
    )
    (net (code "106") (name "unconnected-(Arduino-Pad45)") (class "Default")
      (node (ref "Arduino") (pin "45") (pinfunction "45_45") (pintype "passive"))
    )
    (net (code "107") (name "unconnected-(Arduino-Pad46)") (class "Default")
      (node (ref "Arduino") (pin "46") (pinfunction "46_46") (pintype "passive"))
    )
    (net (code "108") (name "unconnected-(Arduino-Pad47)") (class "Default")
      (node (ref "Arduino") (pin "47") (pinfunction "47_47") (pintype "passive"))
    )
    (net (code "109") (name "unconnected-(Arduino-Pad48)") (class "Default")
      (node (ref "Arduino") (pin "48") (pinfunction "48_48") (pintype "passive"))
    )
    (net (code "110") (name "unconnected-(Arduino-Pad49)") (class "Default")
      (node (ref "Arduino") (pin "49") (pinfunction "49_49") (pintype "passive"))
    )
    (net (code "111") (name "unconnected-(Arduino-PadA0)") (class "Default")
      (node (ref "Arduino") (pin "A0") (pinfunction "A0_A0") (pintype "passive"))
    )
    (net (code "112") (name "unconnected-(Arduino-PadA1)") (class "Default")
      (node (ref "Arduino") (pin "A1") (pinfunction "A1_A1") (pintype "passive"))
    )
    (net (code "113") (name "unconnected-(Arduino-PadA2)") (class "Default")
      (node (ref "Arduino") (pin "A2") (pinfunction "A2_A2") (pintype "passive"))
    )
    (net (code "114") (name "unconnected-(Arduino-PadA3)") (class "Default")
      (node (ref "Arduino") (pin "A3") (pinfunction "A3_A3") (pintype "passive"))
    )
    (net (code "115") (name "unconnected-(Arduino-PadA4)") (class "Default")
      (node (ref "Arduino") (pin "A4") (pinfunction "A4_A4") (pintype "passive"))
    )
    (net (code "116") (name "unconnected-(Arduino-PadA5)") (class "Default")
      (node (ref "Arduino") (pin "A5") (pinfunction "A5_A5") (pintype "passive"))
    )
    (net (code "117") (name "unconnected-(Arduino-PadA6)") (class "Default")
      (node (ref "Arduino") (pin "A6") (pinfunction "A6_A6") (pintype "passive"))
    )
    (net (code "118") (name "unconnected-(Arduino-PadA7)") (class "Default")
      (node (ref "Arduino") (pin "A7") (pinfunction "A7_A7") (pintype "passive"))
    )
    (net (code "119") (name "unconnected-(Arduino-PadA8)") (class "Default")
      (node (ref "Arduino") (pin "A8") (pinfunction "A8_A8") (pintype "passive"))
    )
    (net (code "120") (name "unconnected-(Arduino-PadA9)") (class "Default")
      (node (ref "Arduino") (pin "A9") (pinfunction "A9_A9") (pintype "passive"))
    )
    (net (code "121") (name "unconnected-(Arduino-PadA10)") (class "Default")
      (node (ref "Arduino") (pin "A10") (pinfunction "A10_A10") (pintype "passive"))
    )
    (net (code "122") (name "unconnected-(Arduino-PadA11)") (class "Default")
      (node (ref "Arduino") (pin "A11") (pinfunction "A11_A11") (pintype "passive"))
    )
    (net (code "123") (name "unconnected-(Arduino-PadA12)") (class "Default")
      (node (ref "Arduino") (pin "A12") (pinfunction "A12_A12") (pintype "passive"))
    )
    (net (code "124") (name "unconnected-(Arduino-PadA13)") (class "Default")
      (node (ref "Arduino") (pin "A13") (pinfunction "A13_A13") (pintype "passive"))
    )
    (net (code "125") (name "unconnected-(Arduino-PadA14)") (class "Default")
      (node (ref "Arduino") (pin "A14") (pinfunction "A14_A14") (pintype "passive"))
    )
    (net (code "126") (name "unconnected-(Arduino-PadA15)") (class "Default")
      (node (ref "Arduino") (pin "A15") (pinfunction "A15_A15") (pintype "passive"))
    )
    (net (code "127") (name "unconnected-(Arduino-PadAREF)") (class "Default")
      (node (ref "Arduino") (pin "AREF") (pinfunction "AREF_AREF") (pintype "passive"))
    )
    (net (code "128") (name "unconnected-(Arduino-PadGND)") (class "Default")
      (node (ref "Arduino") (pin "GND") (pinfunction "GND_GND") (pintype "passive"))
    )
    (net (code "129") (name "unconnected-(Arduino-PadGND)_1") (class "Default")
      (node (ref "Arduino") (pin "GND") (pinfunction "GND_GND") (pintype "passive"))
    )
    (net (code "130") (name "unconnected-(Arduino-PadIOREF)") (class "Default")
      (node (ref "Arduino") (pin "IOREF") (pinfunction "IOREF_IOREF") (pintype "passive"))
    )
    (net (code "131") (name "unconnected-(Arduino-PadMISO)") (class "Default")
      (node (ref "Arduino") (pin "MISO") (pinfunction "MISO_MISO") (pintype "passive"))
    )
    (net (code "132") (name "unconnected-(Arduino-PadMOSI)") (class "Default")
      (node (ref "Arduino") (pin "MOSI") (pinfunction "MOSI_MOSI") (pintype "passive"))
    )
    (net (code "133") (name "unconnected-(Arduino-PadRESET)") (class "Default")
      (node (ref "Arduino") (pin "RESET") (pinfunction "RESET_RESET") (pintype "passive"))
    )
    (net (code "134") (name "unconnected-(Arduino-PadRST)") (class "Default")
      (node (ref "Arduino") (pin "RST") (pinfunction "RST_RST") (pintype "passive"))
    )
    (net (code "135") (name "unconnected-(Arduino-PadSCK)") (class "Default")
      (node (ref "Arduino") (pin "SCK") (pinfunction "SCK_SCK") (pintype "passive"))
    )
    (net (code "136") (name "unconnected-(Arduino-PadVCC)") (class "Default")
      (node (ref "Arduino") (pin "VCC") (pinfunction "VCC_VCC") (pintype "passive"))
    )
    (net (code "137") (name "unconnected-(Arduino-PadVIN)") (class "Default")
      (node (ref "Arduino") (pin "VIN") (pinfunction "VIN_VIN") (pintype "passive"))
    )
    (net (code "138") (name "unconnected-(Compas-3VO-Pad3)") (class "Default")
      (node (ref "Compas") (pin "3") (pinfunction "3VO_3") (pintype "passive"))
    )
    (net (code "139") (name "unconnected-(Compas-RDY-Pad0)") (class "Default")
      (node (ref "Compas") (pin "0") (pinfunction "RDY_0") (pintype "passive"))
    )
    (net (code "140") (name "unconnected-(Compas-VIN-Pad5)") (class "Default")
      (node (ref "Compas") (pin "5") (pinfunction "VIN_5") (pintype "passive"))
    )
    (net (code "141") (name "unconnected-(Pot-Prot-Top-Pad1)") (class "Default")
      (node (ref "Pot-Prot") (pin "1") (pinfunction "Top_1") (pintype "passive"))
    )
    (net (code "142") (name "unconnected-(RFD-CTS-Pad3)") (class "Default")
      (node (ref "RFD") (pin "3") (pinfunction "CTS_3") (pintype "passive"))
    )
    (net (code "143") (name "unconnected-(RFD-P0.1-Pad13)") (class "Default")
      (node (ref "RFD") (pin "13") (pinfunction "P0.1_13") (pintype "passive"))
    )
    (net (code "144") (name "unconnected-(RFD-P2.0-Pad14)") (class "Default")
      (node (ref "RFD") (pin "14") (pinfunction "P2.0_14") (pintype "passive"))
    )
    (net (code "145") (name "unconnected-(RFD-P2.1-Pad12)") (class "Default")
      (node (ref "RFD") (pin "12") (pinfunction "P2.1_12") (pintype "passive"))
    )
    (net (code "146") (name "unconnected-(RFD-P2.2-Pad10)") (class "Default")
      (node (ref "RFD") (pin "10") (pinfunction "P2.2_10") (pintype "passive"))
    )
    (net (code "147") (name "unconnected-(RFD-P2.3-Pad8)") (class "Default")
      (node (ref "RFD") (pin "8") (pinfunction "P2.3_8") (pintype "passive"))
    )
    (net (code "148") (name "unconnected-(RFD-P2.6-Pad15)") (class "Default")
      (node (ref "RFD") (pin "15") (pinfunction "P2.6_15") (pintype "passive"))
    )
    (net (code "149") (name "unconnected-(RFD-RTS-Pad11)") (class "Default")
      (node (ref "RFD") (pin "11") (pinfunction "RTS_11") (pintype "passive"))
    )
    (net (code "150") (name "unconnected-(RFD-Vusb-Pad5)") (class "Default")
      (node (ref "RFD") (pin "5") (pinfunction "Vusb_5") (pintype "passive"))
    )
    (net (code "151") (name "unconnected-(RFD-Vusb-Pad6)") (class "Default")
      (node (ref "RFD") (pin "6") (pinfunction "Vusb_6") (pintype "passive"))
    )
    (net (code "152") (name "unconnected-(SDsocket-CARD_DETECT-Pad9)") (class "Default")
      (node (ref "SDsocket") (pin "9") (pinfunction "CARD_DETECT_9") (pintype "bidirectional"))
    )
    (net (code "153") (name "unconnected-(SDsocket-CARD_DETECT-Pad10)") (class "Default")
      (node (ref "SDsocket") (pin "10") (pinfunction "CARD_DETECT_10") (pintype "bidirectional"))
    )
    (net (code "154") (name "unconnected-(SDsocket-CVDD-Pad4)") (class "Default")
      (node (ref "SDsocket") (pin "4") (pinfunction "CVDD_4") (pintype "power_in"))
    )
    (net (code "155") (name "unconnected-(SDsocket-DAT1-Pad8)") (class "Default")
      (node (ref "SDsocket") (pin "8") (pinfunction "DAT1_8") (pintype "bidirectional"))
    )
    (net (code "156") (name "unconnected-(SDsocket-DAT2-Pad1)") (class "Default")
      (node (ref "SDsocket") (pin "1") (pinfunction "DAT2_1") (pintype "bidirectional"))
    )
    (net (code "157") (name "unconnected-(gps-SCL-Pad5)") (class "Default")
      (node (ref "gps") (pin "5") (pinfunction "SCL_5") (pintype "passive"))
    )
    (net (code "158") (name "unconnected-(gps-SDA-Pad6)") (class "Default")
      (node (ref "gps") (pin "6") (pinfunction "SDA_6") (pintype "passive"))
    )
    (net (code "159") (name "unconnected-(gps-T_P-Pad1)") (class "Default")
      (node (ref "gps") (pin "1") (pinfunction "T_P_1") (pintype "passive"))
    )
  )
)
